# LEDS.net
KiCad netlist of a schematic drawn in Altium Designer
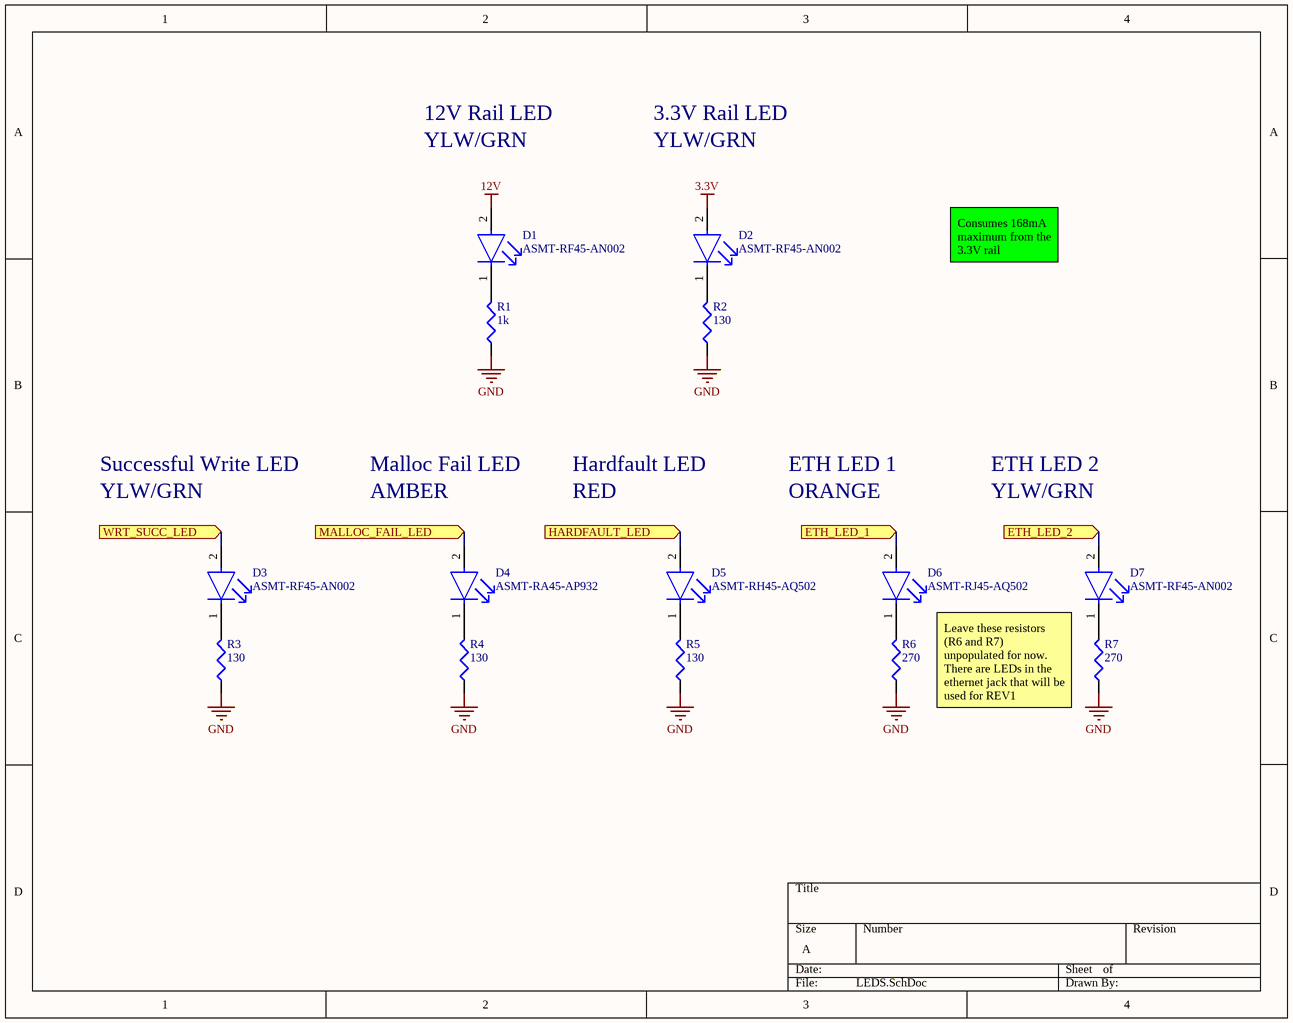
[diagram p0: LEDS.SchDoc]

(export (version "E")
  (design (tool "Eeschema 10.0.6"))
  (components
    (comp (ref "D1")
      (value "ASMT-RF45-AN002")
      (footprint "FP-ASMT-RF45-AN002-MFG")
      (description "LED YLW/GREEN DIFFUSED 0603 SMD")
      (fields
        (field (name "MANUFACTURER") "Broadcom")
        (field (name "OCTOPART") "https://octopart.com/asmt-rf45-an002-broadcom-71127304")
      )
      (libsource (lib "Altium Content Vault") (part "8706943c75ba83719d021d2fdc84c58"))
    )
    (comp (ref "D2")
      (value "ASMT-RF45-AN002")
      (footprint "FP-ASMT-RF45-AN002-MFG")
      (description "LED YLW/GREEN DIFFUSED 0603 SMD")
      (fields
        (field (name "MANUFACTURER") "Broadcom")
        (field (name "OCTOPART") "https://octopart.com/asmt-rf45-an002-broadcom-71127304")
      )
      (libsource (lib "Altium Content Vault") (part "8706943c75ba83719d021d2fdc84c58"))
    )
    (comp (ref "D3")
      (value "ASMT-RF45-AN002")
      (footprint "FP-ASMT-RF45-AN002-MFG")
      (description "LED YLW/GREEN DIFFUSED 0603 SMD")
      (fields
        (field (name "MANUFACTURER") "Broadcom")
        (field (name "OCTOPART") "https://octopart.com/asmt-rf45-an002-broadcom-71127304")
      )
      (libsource (lib "Altium Content Vault") (part "8706943c75ba83719d021d2fdc84c58"))
    )
    (comp (ref "D4")
      (value "ASMT-RA45-AP932")
      (footprint "FP-ASMT-RF45-AN002-MFG")
      (description "LED AMBER DIFFUSED SMD")
      (fields
        (field (name "MANUFACTURER") "Broadcom")
        (field (name "OCTOPART") "https://octopart.com/asmt-rf45-an002-broadcom-71127304")
      )
      (libsource (lib "Altium Content Vault") (part "8706943c75ba83719d021d2fdc84c58"))
    )
    (comp (ref "D5")
      (value "ASMT-RH45-AQ502")
      (footprint "FP-ASMT-RF45-AN002-MFG")
      (description "LED RED DIFFUSED 0603 SMD")
      (fields
        (field (name "MANUFACTURER") "Broadcom")
        (field (name "OCTOPART") "https://octopart.com/asmt-rf45-an002-broadcom-71127304")
      )
      (libsource (lib "Altium Content Vault") (part "8706943c75ba83719d021d2fdc84c58"))
    )
    (comp (ref "D6")
      (value "ASMT-RJ45-AQ502")
      (footprint "FP-ASMT-RF45-AN002-MFG")
      (description "LED ORANGE DIFFUSED 0603 SMD")
      (fields
        (field (name "MANUFACTURER") "Broadcom")
        (field (name "OCTOPART") "https://octopart.com/asmt-rf45-an002-broadcom-71127304")
      )
      (libsource (lib "Altium Content Vault") (part "8706943c75ba83719d021d2fdc84c58"))
    )
    (comp (ref "D7")
      (value "ASMT-RF45-AN002")
      (footprint "FP-ASMT-RF45-AN002-MFG")
      (description "LED YLW/GREEN DIFFUSED 0603 SMD")
      (fields
        (field (name "MANUFACTURER") "Broadcom")
        (field (name "OCTOPART") "https://octopart.com/asmt-rf45-an002-broadcom-71127304")
      )
      (libsource (lib "Altium Content Vault") (part "8706943c75ba83719d021d2fdc84c58"))
    )
    (comp (ref "R1")
      (value "1k")
      (footprint "J1-0603")
      (description "Resistor")
      (fields (field (name "PUBLISHER") "Altium Limited"))
      (libsource (lib "Miscellaneous Devices") (part "Res3"))
    )
    (comp (ref "R2")
      (value "130")
      (footprint "J1-0603")
      (description "Resistor")
      (fields (field (name "PUBLISHER") "Altium Limited"))
      (libsource (lib "Miscellaneous Devices") (part "Res3"))
    )
    (comp (ref "R3")
      (value "130")
      (footprint "J1-0603")
      (description "Resistor")
      (fields (field (name "PUBLISHER") "Altium Limited"))
      (libsource (lib "Miscellaneous Devices") (part "Res3"))
    )
    (comp (ref "R4")
      (value "130")
      (footprint "J1-0603")
      (description "Resistor")
      (fields (field (name "PUBLISHER") "Altium Limited"))
      (libsource (lib "Miscellaneous Devices") (part "Res3"))
    )
    (comp (ref "R5")
      (value "130")
      (footprint "J1-0603")
      (description "Resistor")
      (fields (field (name "PUBLISHER") "Altium Limited"))
      (libsource (lib "Miscellaneous Devices") (part "Res3"))
    )
    (comp (ref "R6")
      (value "270")
      (footprint "J1-0603")
      (description "Resistor")
      (fields (field (name "PUBLISHER") "Altium Limited"))
      (libsource (lib "Miscellaneous Devices") (part "Res3"))
    )
    (comp (ref "R7")
      (value "270")
      (footprint "J1-0603")
      (description "Resistor")
      (fields (field (name "PUBLISHER") "Altium Limited"))
      (libsource (lib "Miscellaneous Devices") (part "Res3"))
    )
  )
  (nets
    (net (code "1") (name "/ETH_LED_1") (class "Default")
      (node (ref "D6") (pin "2") (pinfunction "A_2") (pintype "passive"))
    )
    (net (code "2") (name "/ETH_LED_2") (class "Default")
      (node (ref "D7") (pin "2") (pinfunction "A_2") (pintype "passive"))
    )
    (net (code "3") (name "/HARDFAULT_LED") (class "Default")
      (node (ref "D5") (pin "2") (pinfunction "A_2") (pintype "passive"))
    )
    (net (code "4") (name "/MALLOC_FAIL_LED") (class "Default")
      (node (ref "D4") (pin "2") (pinfunction "A_2") (pintype "passive"))
    )
    (net (code "5") (name "/WRT_SUCC_LED") (class "Default")
      (node (ref "D3") (pin "2") (pinfunction "A_2") (pintype "passive"))
    )
    (net (code "6") (name "3.3V") (class "Default")
      (node (ref "D2") (pin "2") (pinfunction "A_2") (pintype "passive"))
    )
    (net (code "7") (name "12V") (class "Default")
      (node (ref "D1") (pin "2") (pinfunction "A_2") (pintype "passive"))
    )
    (net (code "8") (name "GND") (class "Default")
      (node (ref "R1") (pin "1") (pinfunction "1_1") (pintype "passive"))
      (node (ref "R2") (pin "1") (pinfunction "1_1") (pintype "passive"))
      (node (ref "R3") (pin "1") (pinfunction "1_1") (pintype "passive"))
      (node (ref "R4") (pin "1") (pinfunction "1_1") (pintype "passive"))
      (node (ref "R5") (pin "1") (pinfunction "1_1") (pintype "passive"))
      (node (ref "R6") (pin "1") (pinfunction "1_1") (pintype "passive"))
      (node (ref "R7") (pin "1") (pinfunction "1_1") (pintype "passive"))
    )
    (net (code "9") (name "Net-(D1-C)") (class "Default")
      (node (ref "D1") (pin "1") (pinfunction "C_1") (pintype "passive"))
      (node (ref "R1") (pin "2") (pinfunction "2_2") (pintype "passive"))
    )
    (net (code "10") (name "Net-(D2-C)") (class "Default")
      (node (ref "D2") (pin "1") (pinfunction "C_1") (pintype "passive"))
      (node (ref "R2") (pin "2") (pinfunction "2_2") (pintype "passive"))
    )
    (net (code "11") (name "Net-(D3-C)") (class "Default")
      (node (ref "D3") (pin "1") (pinfunction "C_1") (pintype "passive"))
      (node (ref "R3") (pin "2") (pinfunction "2_2") (pintype "passive"))
    )
    (net (code "12") (name "Net-(D4-C)") (class "Default")
      (node (ref "D4") (pin "1") (pinfunction "C_1") (pintype "passive"))
      (node (ref "R4") (pin "2") (pinfunction "2_2") (pintype "passive"))
    )
    (net (code "13") (name "Net-(D5-C)") (class "Default")
      (node (ref "D5") (pin "1") (pinfunction "C_1") (pintype "passive"))
      (node (ref "R5") (pin "2") (pinfunction "2_2") (pintype "passive"))
    )
    (net (code "14") (name "Net-(D6-C)") (class "Default")
      (node (ref "D6") (pin "1") (pinfunction "C_1") (pintype "passive"))
      (node (ref "R6") (pin "2") (pinfunction "2_2") (pintype "passive"))
    )
    (net (code "15") (name "Net-(D7-C)") (class "Default")
      (node (ref "D7") (pin "1") (pinfunction "C_1") (pintype "passive"))
      (node (ref "R7") (pin "2") (pinfunction "2_2") (pintype "passive"))
    )
  )
)
